# Qwiic_1Wire_to_I2C_Bridge_DS28E17.net
KiCad netlist of a schematic drawn in EAGLE
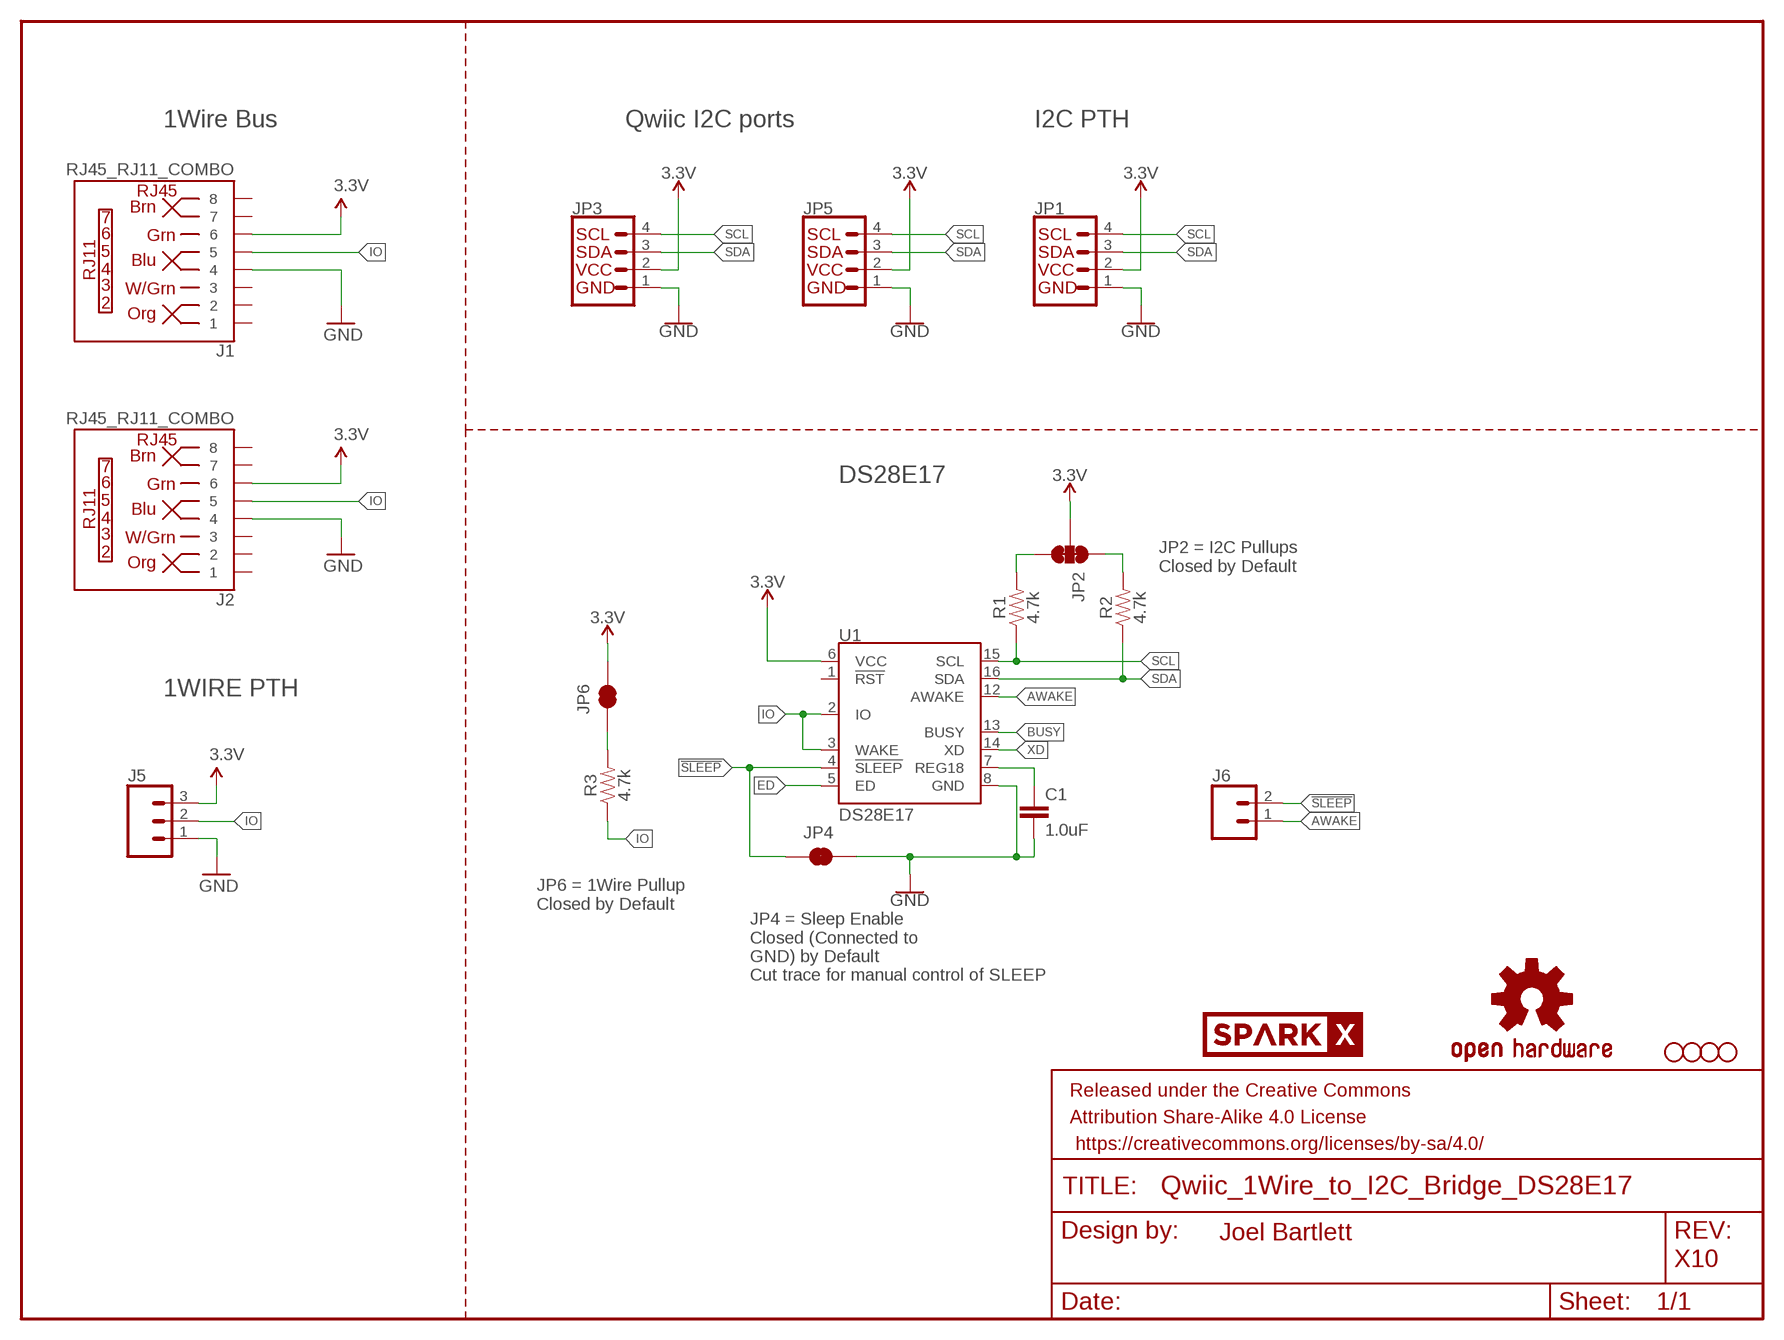
[diagram p0: schematic, sheet 1]

(export (version "E")
  (design (tool "Eeschema 10.0.6"))
  (components
    (comp (ref "C1")
      (value "1.0uF")
      (footprint "eagle-import:0603")
      (libsource (lib "eagle-import") (part "1.0UF-0603-16V-10%"))
    )
    (comp (ref "FRAME1")
      (value "FRAME-LETTER")
      (footprint "eagle-import:CREATIVE_COMMONS")
      (libsource (lib "eagle-import") (part "FRAME-LETTER"))
    )
    (comp (ref "H1")
      (value "STAND-OFF")
      (footprint "eagle-import:STAND-OFF")
      (libsource (lib "eagle-import") (part "STAND-OFF"))
    )
    (comp (ref "H2")
      (value "STAND-OFF")
      (footprint "eagle-import:STAND-OFF")
      (libsource (lib "eagle-import") (part "STAND-OFF"))
    )
    (comp (ref "H3")
      (value "STAND-OFF")
      (footprint "eagle-import:STAND-OFF")
      (libsource (lib "eagle-import") (part "STAND-OFF"))
    )
    (comp (ref "H4")
      (value "STAND-OFF")
      (footprint "eagle-import:STAND-OFF")
      (libsource (lib "eagle-import") (part "STAND-OFF"))
    )
    (comp (ref "J1")
      (value "RJ45_RJ11_COMBO")
      (footprint "eagle-import:RJ45_RJ11_COMBO")
      (libsource (lib "eagle-import") (part "RJ45_RJ11_COMBO"))
    )
    (comp (ref "J2")
      (value "RJ45_RJ11_COMBO")
      (footprint "eagle-import:RJ45_RJ11_COMBO")
      (libsource (lib "eagle-import") (part "RJ45_RJ11_COMBO"))
    )
    (comp (ref "J5")
      (value "CONN_03")
      (footprint "eagle-import:1X03")
      (libsource (lib "eagle-import") (part "CONN_03"))
    )
    (comp (ref "J6")
      (value "CONN_02")
      (footprint "eagle-import:1X02")
      (libsource (lib "eagle-import") (part "CONN_02"))
    )
    (comp (ref "JP1")
      (value "I2C_STANDARDSILK")
      (footprint "eagle-import:1X04")
      (libsource (lib "eagle-import") (part "I2C_STANDARDSILK"))
    )
    (comp (ref "JP2")
      (value "JUMPER-SMT_3_2-NC_TRACE_SILK")
      (footprint "eagle-import:SMT-JUMPER_3_2-NC_TRACE_SILK")
      (libsource (lib "eagle-import") (part "JUMPER-SMT_3_2-NC_TRACE_SILK"))
    )
    (comp (ref "JP3")
      (value "I2C_STANDARDJS-1MM")
      (footprint "eagle-import:1X04_1MM_RA")
      (libsource (lib "eagle-import") (part "I2C_STANDARDJS-1MM"))
    )
    (comp (ref "JP4")
      (value "JUMPER-SMT_2_NC_TRACE_SILK")
      (footprint "eagle-import:SMT-JUMPER_2_NC_TRACE_SILK")
      (libsource (lib "eagle-import") (part "JUMPER-SMT_2_NC_TRACE_SILK"))
    )
    (comp (ref "JP5")
      (value "I2C_STANDARDJS-1MM")
      (footprint "eagle-import:1X04_1MM_RA")
      (libsource (lib "eagle-import") (part "I2C_STANDARDJS-1MM"))
    )
    (comp (ref "JP6")
      (value "JUMPER-SMT_2_NC_TRACE_SILK")
      (footprint "eagle-import:SMT-JUMPER_2_NC_TRACE_SILK")
      (libsource (lib "eagle-import") (part "JUMPER-SMT_2_NC_TRACE_SILK"))
    )
    (comp (ref "LOGO1")
      (value "OSHW-LOGOM")
      (footprint "eagle-import:OSHW-LOGO-M")
      (libsource (lib "eagle-import") (part "OSHW-LOGOM"))
    )
    (comp (ref "R1")
      (value "4.7k")
      (footprint "eagle-import:0603")
      (libsource (lib "eagle-import") (part "4.7KOHM-0603-1/10W-1%"))
    )
    (comp (ref "R2")
      (value "4.7k")
      (footprint "eagle-import:0603")
      (libsource (lib "eagle-import") (part "4.7KOHM-0603-1/10W-1%"))
    )
    (comp (ref "R3")
      (value "4.7k")
      (footprint "eagle-import:0603")
      (libsource (lib "eagle-import") (part "4.7KOHM-0603-1/10W-1%"))
    )
    (comp (ref "U$2")
      (value "SPARKX-LOGO5")
      (footprint "eagle-import:SPARKX-LARGE")
      (libsource (lib "eagle-import") (part "SPARKX-LOGO5"))
    )
    (comp (ref "U$3")
      (value "SPARKX-LOGO5")
      (footprint "eagle-import:SPARKX-LARGE")
      (libsource (lib "eagle-import") (part "SPARKX-LOGO5"))
    )
    (comp (ref "U1")
      (value "DS28E17")
      (footprint "eagle-import:TQFN-16")
      (libsource (lib "eagle-import") (part "DS28E17"))
    )
  )
  (nets
    (net (code "1") (name "/~{SLEEP}") (class "Default")
      (node (ref "J6") (pin "2") (pinfunction "2_2") (pintype "passive"))
      (node (ref "JP4") (pin "1") (pinfunction "1_1") (pintype "passive"))
      (node (ref "U1") (pin "4") (pinfunction "~{SLEEP}_4") (pintype "bidirectional"))
    )
    (net (code "2") (name "3.3V") (class "Default")
      (node (ref "J1") (pin "6") (pinfunction "6_6") (pintype "bidirectional"))
      (node (ref "J2") (pin "6") (pinfunction "6_6") (pintype "bidirectional"))
      (node (ref "J5") (pin "3") (pinfunction "3_3") (pintype "passive"))
      (node (ref "JP1") (pin "2") (pinfunction "VCC_2") (pintype "power_in"))
      (node (ref "JP2") (pin "2") (pinfunction "2_2") (pintype "passive"))
      (node (ref "JP3") (pin "2") (pinfunction "VCC_2") (pintype "power_in"))
      (node (ref "JP5") (pin "2") (pinfunction "VCC_2") (pintype "power_in"))
      (node (ref "JP6") (pin "2") (pinfunction "2_2") (pintype "passive"))
      (node (ref "U1") (pin "6") (pinfunction "VCC_6") (pintype "power_in"))
    )
    (net (code "3") (name "AWAKE") (class "Default")
      (node (ref "J6") (pin "1") (pinfunction "1_1") (pintype "passive"))
      (node (ref "U1") (pin "12") (pinfunction "AWAKE_12") (pintype "bidirectional"))
    )
    (net (code "4") (name "BUSY") (class "Default")
      (node (ref "U1") (pin "13") (pinfunction "BUSY_13") (pintype "bidirectional"))
    )
    (net (code "5") (name "ED") (class "Default")
      (node (ref "U1") (pin "5") (pinfunction "ED_5") (pintype "bidirectional"))
    )
    (net (code "6") (name "GND") (class "Default")
      (node (ref "C1") (pin "2") (pinfunction "2_2") (pintype "passive"))
      (node (ref "J1") (pin "4") (pinfunction "4_4") (pintype "bidirectional"))
      (node (ref "J2") (pin "4") (pinfunction "4_4") (pintype "bidirectional"))
      (node (ref "J5") (pin "1") (pinfunction "1_1") (pintype "passive"))
      (node (ref "JP1") (pin "1") (pinfunction "GND_1") (pintype "power_in"))
      (node (ref "JP3") (pin "1") (pinfunction "GND_1") (pintype "power_in"))
      (node (ref "JP4") (pin "2") (pinfunction "2_2") (pintype "passive"))
      (node (ref "JP5") (pin "1") (pinfunction "GND_1") (pintype "power_in"))
      (node (ref "U1") (pin "8") (pinfunction "GND_8") (pintype "power_in"))
    )
    (net (code "7") (name "IO") (class "Default")
      (node (ref "J1") (pin "5") (pinfunction "5_5") (pintype "bidirectional"))
      (node (ref "J2") (pin "5") (pinfunction "5_5") (pintype "bidirectional"))
      (node (ref "J5") (pin "2") (pinfunction "2_2") (pintype "passive"))
      (node (ref "R3") (pin "1") (pinfunction "1_1") (pintype "passive"))
      (node (ref "U1") (pin "2") (pinfunction "IO_2") (pintype "bidirectional"))
      (node (ref "U1") (pin "3") (pinfunction "WAKE_3") (pintype "bidirectional"))
    )
    (net (code "8") (name "Net-(JP2-Pad1)") (class "Default")
      (node (ref "JP2") (pin "1") (pinfunction "1_1") (pintype "passive"))
      (node (ref "R2") (pin "2") (pinfunction "2_2") (pintype "passive"))
    )
    (net (code "9") (name "Net-(JP2-Pad3)") (class "Default")
      (node (ref "JP2") (pin "3") (pinfunction "3_3") (pintype "passive"))
      (node (ref "R1") (pin "2") (pinfunction "2_2") (pintype "passive"))
    )
    (net (code "10") (name "Net-(JP6-Pad1)") (class "Default")
      (node (ref "JP6") (pin "1") (pinfunction "1_1") (pintype "passive"))
      (node (ref "R3") (pin "2") (pinfunction "2_2") (pintype "passive"))
    )
    (net (code "11") (name "Net-(U1-REG18)") (class "Default")
      (node (ref "C1") (pin "1") (pinfunction "1_1") (pintype "passive"))
      (node (ref "U1") (pin "7") (pinfunction "REG18_7") (pintype "bidirectional"))
    )
    (net (code "12") (name "SCL") (class "Default")
      (node (ref "JP1") (pin "4") (pinfunction "SCL_4") (pintype "passive"))
      (node (ref "JP3") (pin "4") (pinfunction "SCL_4") (pintype "passive"))
      (node (ref "JP5") (pin "4") (pinfunction "SCL_4") (pintype "passive"))
      (node (ref "R1") (pin "1") (pinfunction "1_1") (pintype "passive"))
      (node (ref "U1") (pin "15") (pinfunction "SCL_15") (pintype "bidirectional"))
    )
    (net (code "13") (name "SDA") (class "Default")
      (node (ref "JP1") (pin "3") (pinfunction "SDA_3") (pintype "passive"))
      (node (ref "JP3") (pin "3") (pinfunction "SDA_3") (pintype "passive"))
      (node (ref "JP5") (pin "3") (pinfunction "SDA_3") (pintype "passive"))
      (node (ref "R2") (pin "1") (pinfunction "1_1") (pintype "passive"))
      (node (ref "U1") (pin "16") (pinfunction "SDA_16") (pintype "bidirectional"))
    )
    (net (code "14") (name "XD") (class "Default")
      (node (ref "U1") (pin "14") (pinfunction "XD_14") (pintype "bidirectional"))
    )
    (net (code "15") (name "unconnected-(J1-Pad1)") (class "Default")
      (node (ref "J1") (pin "1") (pinfunction "1_1") (pintype "bidirectional"))
    )
    (net (code "16") (name "unconnected-(J1-Pad2)") (class "Default")
      (node (ref "J1") (pin "2") (pinfunction "2_2") (pintype "bidirectional"))
    )
    (net (code "17") (name "unconnected-(J1-Pad3)") (class "Default")
      (node (ref "J1") (pin "3") (pinfunction "3_3") (pintype "bidirectional"))
    )
    (net (code "18") (name "unconnected-(J1-Pad7)") (class "Default")
      (node (ref "J1") (pin "7") (pinfunction "7_7") (pintype "bidirectional"))
    )
    (net (code "19") (name "unconnected-(J1-Pad8)") (class "Default")
      (node (ref "J1") (pin "8") (pinfunction "8_8") (pintype "bidirectional"))
    )
    (net (code "20") (name "unconnected-(J2-Pad1)") (class "Default")
      (node (ref "J2") (pin "1") (pinfunction "1_1") (pintype "bidirectional"))
    )
    (net (code "21") (name "unconnected-(J2-Pad2)") (class "Default")
      (node (ref "J2") (pin "2") (pinfunction "2_2") (pintype "bidirectional"))
    )
    (net (code "22") (name "unconnected-(J2-Pad3)") (class "Default")
      (node (ref "J2") (pin "3") (pinfunction "3_3") (pintype "bidirectional"))
    )
    (net (code "23") (name "unconnected-(J2-Pad7)") (class "Default")
      (node (ref "J2") (pin "7") (pinfunction "7_7") (pintype "bidirectional"))
    )
    (net (code "24") (name "unconnected-(J2-Pad8)") (class "Default")
      (node (ref "J2") (pin "8") (pinfunction "8_8") (pintype "bidirectional"))
    )
    (net (code "25") (name "unconnected-(U1-~{RST}-Pad1)") (class "Default")
      (node (ref "U1") (pin "1") (pinfunction "~{RST}_1") (pintype "bidirectional"))
    )
  )
)
